# protoboard.net
KiCad netlist of a schematic drawn in Altium Designer
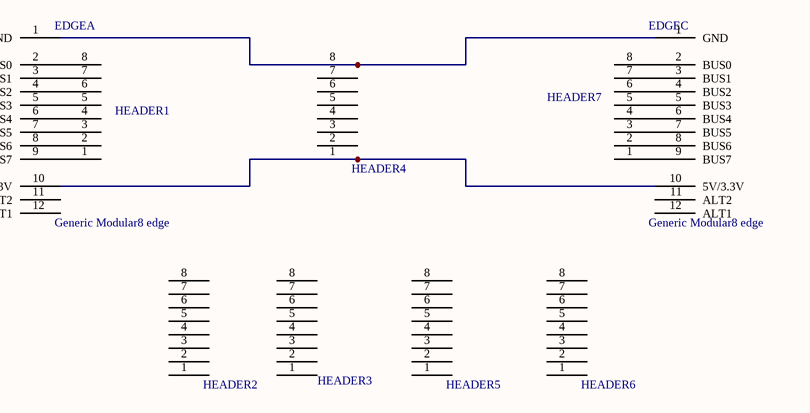
[diagram p0: protoboard.SchDoc]

(export (version "E")
  (design (tool "Eeschema 10.0.6"))
  (components
    (comp (ref "EDGEA")
      (value "Generic Modular8 edge")
      (footprint "MODULAR8 VERTICAL PINS")
      (libsource (lib "OpBots") (part "Generic Modular8 edge"))
    )
    (comp (ref "EDGEC")
      (value "Generic Modular8 edge")
      (footprint "MODULAR8 VERTICAL PINS")
      (libsource (lib "OpBots") (part "Generic Modular8 edge"))
    )
    (comp (ref "HEADER1")
      (value "8x1")
      (footprint "8x1 THRU HOLES 0.1\" PITCH")
      (libsource (lib "OpBots") (part "8x1"))
    )
    (comp (ref "HEADER2")
      (value "8x1")
      (footprint "8x1 THRU HOLES 0.1\" PITCH")
      (libsource (lib "OpBots") (part "8x1"))
    )
    (comp (ref "HEADER3")
      (value "8x1")
      (footprint "8x1 THRU HOLES 0.1\" PITCH")
      (libsource (lib "OpBots") (part "8x1"))
    )
    (comp (ref "HEADER4")
      (value "8x1")
      (footprint "8x1 THRU HOLES 0.1\" PITCH")
      (libsource (lib "OpBots") (part "8x1"))
    )
    (comp (ref "HEADER5")
      (value "8x1")
      (footprint "8x1 THRU HOLES 0.1\" PITCH")
      (libsource (lib "OpBots") (part "8x1"))
    )
    (comp (ref "HEADER6")
      (value "8x1")
      (footprint "8x1 THRU HOLES 0.1\" PITCH")
      (libsource (lib "OpBots") (part "8x1"))
    )
    (comp (ref "HEADER7")
      (value "8x1")
      (footprint "8x1 THRU HOLES 0.1\" PITCH")
      (libsource (lib "OpBots") (part "8x1"))
    )
  )
  (nets
    (net (code "1") (name "Net-(EDGEA-5V{slash}3.3V)") (class "Default")
      (node (ref "EDGEA") (pin "10") (pinfunction "5V/3.3V_10") (pintype "passive"))
      (node (ref "EDGEC") (pin "10") (pinfunction "5V/3.3V_10") (pintype "passive"))
      (node (ref "HEADER4") (pin "1") (pintype "passive"))
    )
    (net (code "2") (name "Net-(EDGEA-BUS0)") (class "Default")
      (node (ref "EDGEA") (pin "2") (pinfunction "BUS0_2") (pintype "passive"))
      (node (ref "HEADER1") (pin "8") (pintype "passive"))
    )
    (net (code "3") (name "Net-(EDGEA-BUS1)") (class "Default")
      (node (ref "EDGEA") (pin "3") (pinfunction "BUS1_3") (pintype "passive"))
      (node (ref "HEADER1") (pin "7") (pintype "passive"))
    )
    (net (code "4") (name "Net-(EDGEA-BUS2)") (class "Default")
      (node (ref "EDGEA") (pin "4") (pinfunction "BUS2_4") (pintype "passive"))
      (node (ref "HEADER1") (pin "6") (pintype "passive"))
    )
    (net (code "5") (name "Net-(EDGEA-BUS3)") (class "Default")
      (node (ref "EDGEA") (pin "5") (pinfunction "BUS3_5") (pintype "passive"))
      (node (ref "HEADER1") (pin "5") (pintype "passive"))
    )
    (net (code "6") (name "Net-(EDGEA-BUS4)") (class "Default")
      (node (ref "EDGEA") (pin "6") (pinfunction "BUS4_6") (pintype "passive"))
      (node (ref "HEADER1") (pin "4") (pintype "passive"))
    )
    (net (code "7") (name "Net-(EDGEA-BUS5)") (class "Default")
      (node (ref "EDGEA") (pin "7") (pinfunction "BUS5_7") (pintype "passive"))
      (node (ref "HEADER1") (pin "3") (pintype "passive"))
    )
    (net (code "8") (name "Net-(EDGEA-BUS6)") (class "Default")
      (node (ref "EDGEA") (pin "8") (pinfunction "BUS6_8") (pintype "passive"))
      (node (ref "HEADER1") (pin "2") (pintype "passive"))
    )
    (net (code "9") (name "Net-(EDGEA-BUS7)") (class "Default")
      (node (ref "EDGEA") (pin "9") (pinfunction "BUS7_9") (pintype "passive"))
      (node (ref "HEADER1") (pin "1") (pintype "passive"))
    )
    (net (code "10") (name "Net-(EDGEA-GND)") (class "Default")
      (node (ref "EDGEA") (pin "1") (pinfunction "GND_1") (pintype "passive"))
      (node (ref "EDGEC") (pin "1") (pinfunction "GND_1") (pintype "passive"))
      (node (ref "HEADER4") (pin "8") (pintype "passive"))
    )
    (net (code "11") (name "Net-(EDGEC-BUS0)") (class "Default")
      (node (ref "EDGEC") (pin "2") (pinfunction "BUS0_2") (pintype "passive"))
      (node (ref "HEADER7") (pin "8") (pintype "passive"))
    )
    (net (code "12") (name "Net-(EDGEC-BUS1)") (class "Default")
      (node (ref "EDGEC") (pin "3") (pinfunction "BUS1_3") (pintype "passive"))
      (node (ref "HEADER7") (pin "7") (pintype "passive"))
    )
    (net (code "13") (name "Net-(EDGEC-BUS2)") (class "Default")
      (node (ref "EDGEC") (pin "4") (pinfunction "BUS2_4") (pintype "passive"))
      (node (ref "HEADER7") (pin "6") (pintype "passive"))
    )
    (net (code "14") (name "Net-(EDGEC-BUS3)") (class "Default")
      (node (ref "EDGEC") (pin "5") (pinfunction "BUS3_5") (pintype "passive"))
      (node (ref "HEADER7") (pin "5") (pintype "passive"))
    )
    (net (code "15") (name "Net-(EDGEC-BUS4)") (class "Default")
      (node (ref "EDGEC") (pin "6") (pinfunction "BUS4_6") (pintype "passive"))
      (node (ref "HEADER7") (pin "4") (pintype "passive"))
    )
    (net (code "16") (name "Net-(EDGEC-BUS5)") (class "Default")
      (node (ref "EDGEC") (pin "7") (pinfunction "BUS5_7") (pintype "passive"))
      (node (ref "HEADER7") (pin "3") (pintype "passive"))
    )
    (net (code "17") (name "Net-(EDGEC-BUS6)") (class "Default")
      (node (ref "EDGEC") (pin "8") (pinfunction "BUS6_8") (pintype "passive"))
      (node (ref "HEADER7") (pin "2") (pintype "passive"))
    )
    (net (code "18") (name "Net-(EDGEC-BUS7)") (class "Default")
      (node (ref "EDGEC") (pin "9") (pinfunction "BUS7_9") (pintype "passive"))
      (node (ref "HEADER7") (pin "1") (pintype "passive"))
    )
    (net (code "19") (name "unconnected-(EDGEA-ALT1-Pad12)") (class "Default")
      (node (ref "EDGEA") (pin "12") (pinfunction "ALT1_12") (pintype "passive"))
    )
    (net (code "20") (name "unconnected-(EDGEA-ALT2-Pad11)") (class "Default")
      (node (ref "EDGEA") (pin "11") (pinfunction "ALT2_11") (pintype "passive"))
    )
    (net (code "21") (name "unconnected-(EDGEC-ALT1-Pad12)") (class "Default")
      (node (ref "EDGEC") (pin "12") (pinfunction "ALT1_12") (pintype "passive"))
    )
    (net (code "22") (name "unconnected-(EDGEC-ALT2-Pad11)") (class "Default")
      (node (ref "EDGEC") (pin "11") (pinfunction "ALT2_11") (pintype "passive"))
    )
    (net (code "23") (name "unconnected-(HEADER2-Pad1)") (class "Default")
      (node (ref "HEADER2") (pin "1") (pintype "passive"))
    )
    (net (code "24") (name "unconnected-(HEADER2-Pad2)") (class "Default")
      (node (ref "HEADER2") (pin "2") (pintype "passive"))
    )
    (net (code "25") (name "unconnected-(HEADER2-Pad3)") (class "Default")
      (node (ref "HEADER2") (pin "3") (pintype "passive"))
    )
    (net (code "26") (name "unconnected-(HEADER2-Pad4)") (class "Default")
      (node (ref "HEADER2") (pin "4") (pintype "passive"))
    )
    (net (code "27") (name "unconnected-(HEADER2-Pad5)") (class "Default")
      (node (ref "HEADER2") (pin "5") (pintype "passive"))
    )
    (net (code "28") (name "unconnected-(HEADER2-Pad6)") (class "Default")
      (node (ref "HEADER2") (pin "6") (pintype "passive"))
    )
    (net (code "29") (name "unconnected-(HEADER2-Pad7)") (class "Default")
      (node (ref "HEADER2") (pin "7") (pintype "passive"))
    )
    (net (code "30") (name "unconnected-(HEADER2-Pad8)") (class "Default")
      (node (ref "HEADER2") (pin "8") (pintype "passive"))
    )
    (net (code "31") (name "unconnected-(HEADER3-Pad1)") (class "Default")
      (node (ref "HEADER3") (pin "1") (pintype "passive"))
    )
    (net (code "32") (name "unconnected-(HEADER3-Pad2)") (class "Default")
      (node (ref "HEADER3") (pin "2") (pintype "passive"))
    )
    (net (code "33") (name "unconnected-(HEADER3-Pad3)") (class "Default")
      (node (ref "HEADER3") (pin "3") (pintype "passive"))
    )
    (net (code "34") (name "unconnected-(HEADER3-Pad4)") (class "Default")
      (node (ref "HEADER3") (pin "4") (pintype "passive"))
    )
    (net (code "35") (name "unconnected-(HEADER3-Pad5)") (class "Default")
      (node (ref "HEADER3") (pin "5") (pintype "passive"))
    )
    (net (code "36") (name "unconnected-(HEADER3-Pad6)") (class "Default")
      (node (ref "HEADER3") (pin "6") (pintype "passive"))
    )
    (net (code "37") (name "unconnected-(HEADER3-Pad7)") (class "Default")
      (node (ref "HEADER3") (pin "7") (pintype "passive"))
    )
    (net (code "38") (name "unconnected-(HEADER3-Pad8)") (class "Default")
      (node (ref "HEADER3") (pin "8") (pintype "passive"))
    )
    (net (code "39") (name "unconnected-(HEADER4-Pad2)") (class "Default")
      (node (ref "HEADER4") (pin "2") (pintype "passive"))
    )
    (net (code "40") (name "unconnected-(HEADER4-Pad3)") (class "Default")
      (node (ref "HEADER4") (pin "3") (pintype "passive"))
    )
    (net (code "41") (name "unconnected-(HEADER4-Pad4)") (class "Default")
      (node (ref "HEADER4") (pin "4") (pintype "passive"))
    )
    (net (code "42") (name "unconnected-(HEADER4-Pad5)") (class "Default")
      (node (ref "HEADER4") (pin "5") (pintype "passive"))
    )
    (net (code "43") (name "unconnected-(HEADER4-Pad6)") (class "Default")
      (node (ref "HEADER4") (pin "6") (pintype "passive"))
    )
    (net (code "44") (name "unconnected-(HEADER4-Pad7)") (class "Default")
      (node (ref "HEADER4") (pin "7") (pintype "passive"))
    )
    (net (code "45") (name "unconnected-(HEADER5-Pad1)") (class "Default")
      (node (ref "HEADER5") (pin "1") (pintype "passive"))
    )
    (net (code "46") (name "unconnected-(HEADER5-Pad2)") (class "Default")
      (node (ref "HEADER5") (pin "2") (pintype "passive"))
    )
    (net (code "47") (name "unconnected-(HEADER5-Pad3)") (class "Default")
      (node (ref "HEADER5") (pin "3") (pintype "passive"))
    )
    (net (code "48") (name "unconnected-(HEADER5-Pad4)") (class "Default")
      (node (ref "HEADER5") (pin "4") (pintype "passive"))
    )
    (net (code "49") (name "unconnected-(HEADER5-Pad5)") (class "Default")
      (node (ref "HEADER5") (pin "5") (pintype "passive"))
    )
    (net (code "50") (name "unconnected-(HEADER5-Pad6)") (class "Default")
      (node (ref "HEADER5") (pin "6") (pintype "passive"))
    )
    (net (code "51") (name "unconnected-(HEADER5-Pad7)") (class "Default")
      (node (ref "HEADER5") (pin "7") (pintype "passive"))
    )
    (net (code "52") (name "unconnected-(HEADER5-Pad8)") (class "Default")
      (node (ref "HEADER5") (pin "8") (pintype "passive"))
    )
    (net (code "53") (name "unconnected-(HEADER6-Pad1)") (class "Default")
      (node (ref "HEADER6") (pin "1") (pintype "passive"))
    )
    (net (code "54") (name "unconnected-(HEADER6-Pad2)") (class "Default")
      (node (ref "HEADER6") (pin "2") (pintype "passive"))
    )
    (net (code "55") (name "unconnected-(HEADER6-Pad3)") (class "Default")
      (node (ref "HEADER6") (pin "3") (pintype "passive"))
    )
    (net (code "56") (name "unconnected-(HEADER6-Pad4)") (class "Default")
      (node (ref "HEADER6") (pin "4") (pintype "passive"))
    )
    (net (code "57") (name "unconnected-(HEADER6-Pad5)") (class "Default")
      (node (ref "HEADER6") (pin "5") (pintype "passive"))
    )
    (net (code "58") (name "unconnected-(HEADER6-Pad6)") (class "Default")
      (node (ref "HEADER6") (pin "6") (pintype "passive"))
    )
    (net (code "59") (name "unconnected-(HEADER6-Pad7)") (class "Default")
      (node (ref "HEADER6") (pin "7") (pintype "passive"))
    )
    (net (code "60") (name "unconnected-(HEADER6-Pad8)") (class "Default")
      (node (ref "HEADER6") (pin "8") (pintype "passive"))
    )
  )
)
